# exp30dc.net
KiCad netlist of a schematic drawn in EAGLE
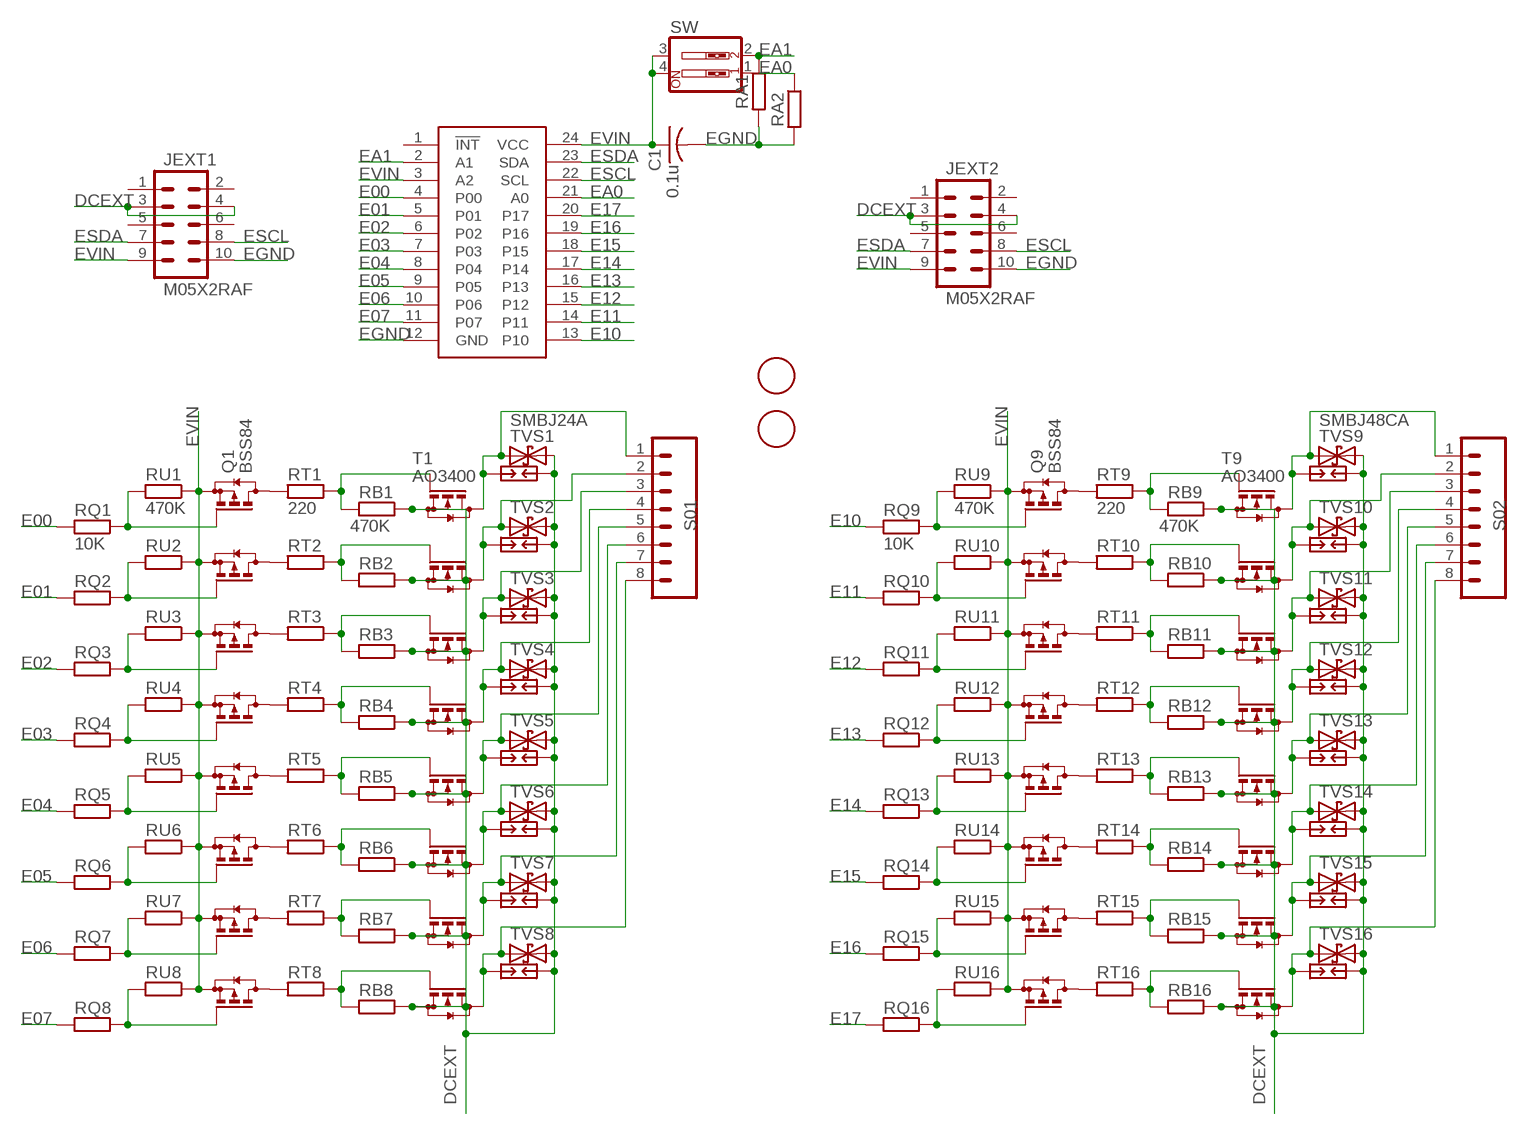
[diagram p0: schematic, sheet 1]

(export (version "E")
  (design (tool "Eeschema 10.0.6"))
  (components
    (comp (ref "C1")
      (value "0.1u")
      (footprint "eagle-import:C0603")
      (libsource (lib "eagle-import") (part "C-USC0603"))
    )
    (comp (ref "JEXT1")
      (value "M05X2RAF")
      (footprint "eagle-import:2X5-RAF")
      (libsource (lib "eagle-import") (part "M05X2RAF"))
    )
    (comp (ref "JEXT2")
      (value "M05X2RAF")
      (footprint "eagle-import:2X5-RAF")
      (libsource (lib "eagle-import") (part "M05X2RAF"))
    )
    (comp (ref "PCF8575")
      (value "PCF8575")
      (footprint "eagle-import:SSOP24")
      (libsource (lib "eagle-import") (part "PCF8575"))
    )
    (comp (ref "Q1")
      (value "BSS84")
      (footprint "eagle-import:SOT23")
      (libsource (lib "eagle-import") (part "BSS84"))
    )
    (comp (ref "Q2")
      (value "BSS84")
      (footprint "eagle-import:SOT23")
      (libsource (lib "eagle-import") (part "BSS84"))
    )
    (comp (ref "Q3")
      (value "BSS84")
      (footprint "eagle-import:SOT23")
      (libsource (lib "eagle-import") (part "BSS84"))
    )
    (comp (ref "Q4")
      (value "BSS84")
      (footprint "eagle-import:SOT23")
      (libsource (lib "eagle-import") (part "BSS84"))
    )
    (comp (ref "Q5")
      (value "BSS84")
      (footprint "eagle-import:SOT23")
      (libsource (lib "eagle-import") (part "BSS84"))
    )
    (comp (ref "Q6")
      (value "BSS84")
      (footprint "eagle-import:SOT23")
      (libsource (lib "eagle-import") (part "BSS84"))
    )
    (comp (ref "Q7")
      (value "BSS84")
      (footprint "eagle-import:SOT23")
      (libsource (lib "eagle-import") (part "BSS84"))
    )
    (comp (ref "Q8")
      (value "BSS84")
      (footprint "eagle-import:SOT23")
      (libsource (lib "eagle-import") (part "BSS84"))
    )
    (comp (ref "Q9")
      (value "BSS84")
      (footprint "eagle-import:SOT23")
      (libsource (lib "eagle-import") (part "BSS84"))
    )
    (comp (ref "Q10")
      (value "BSS84")
      (footprint "eagle-import:SOT23")
      (libsource (lib "eagle-import") (part "BSS84"))
    )
    (comp (ref "Q11")
      (value "BSS84")
      (footprint "eagle-import:SOT23")
      (libsource (lib "eagle-import") (part "BSS84"))
    )
    (comp (ref "Q12")
      (value "BSS84")
      (footprint "eagle-import:SOT23")
      (libsource (lib "eagle-import") (part "BSS84"))
    )
    (comp (ref "Q13")
      (value "BSS84")
      (footprint "eagle-import:SOT23")
      (libsource (lib "eagle-import") (part "BSS84"))
    )
    (comp (ref "Q14")
      (value "BSS84")
      (footprint "eagle-import:SOT23")
      (libsource (lib "eagle-import") (part "BSS84"))
    )
    (comp (ref "Q15")
      (value "BSS84")
      (footprint "eagle-import:SOT23")
      (libsource (lib "eagle-import") (part "BSS84"))
    )
    (comp (ref "Q16")
      (value "BSS84")
      (footprint "eagle-import:SOT23")
      (libsource (lib "eagle-import") (part "BSS84"))
    )
    (comp (ref "RA1")
      (value "10K")
      (footprint "eagle-import:R0603")
      (libsource (lib "eagle-import") (part "R-EU_R0603"))
    )
    (comp (ref "RA2")
      (value "10K")
      (footprint "eagle-import:R0603")
      (libsource (lib "eagle-import") (part "R-EU_R0603"))
    )
    (comp (ref "RB1")
      (value "470K")
      (footprint "eagle-import:R0603")
      (libsource (lib "eagle-import") (part "R-EU_R0603"))
    )
    (comp (ref "RB2")
      (value "470K")
      (footprint "eagle-import:R0603")
      (libsource (lib "eagle-import") (part "R-EU_R0603"))
    )
    (comp (ref "RB3")
      (value "470K")
      (footprint "eagle-import:R0603")
      (libsource (lib "eagle-import") (part "R-EU_R0603"))
    )
    (comp (ref "RB4")
      (value "470K")
      (footprint "eagle-import:R0603")
      (libsource (lib "eagle-import") (part "R-EU_R0603"))
    )
    (comp (ref "RB5")
      (value "470K")
      (footprint "eagle-import:R0603")
      (libsource (lib "eagle-import") (part "R-EU_R0603"))
    )
    (comp (ref "RB6")
      (value "470K")
      (footprint "eagle-import:R0603")
      (libsource (lib "eagle-import") (part "R-EU_R0603"))
    )
    (comp (ref "RB7")
      (value "470K")
      (footprint "eagle-import:R0603")
      (libsource (lib "eagle-import") (part "R-EU_R0603"))
    )
    (comp (ref "RB8")
      (value "470K")
      (footprint "eagle-import:R0603")
      (libsource (lib "eagle-import") (part "R-EU_R0603"))
    )
    (comp (ref "RB9")
      (value "470K")
      (footprint "eagle-import:R0603")
      (libsource (lib "eagle-import") (part "R-EU_R0603"))
    )
    (comp (ref "RB10")
      (value "470K")
      (footprint "eagle-import:R0603")
      (libsource (lib "eagle-import") (part "R-EU_R0603"))
    )
    (comp (ref "RB11")
      (value "470K")
      (footprint "eagle-import:R0603")
      (libsource (lib "eagle-import") (part "R-EU_R0603"))
    )
    (comp (ref "RB12")
      (value "470K")
      (footprint "eagle-import:R0603")
      (libsource (lib "eagle-import") (part "R-EU_R0603"))
    )
    (comp (ref "RB13")
      (value "470K")
      (footprint "eagle-import:R0603")
      (libsource (lib "eagle-import") (part "R-EU_R0603"))
    )
    (comp (ref "RB14")
      (value "470K")
      (footprint "eagle-import:R0603")
      (libsource (lib "eagle-import") (part "R-EU_R0603"))
    )
    (comp (ref "RB15")
      (value "470K")
      (footprint "eagle-import:R0603")
      (libsource (lib "eagle-import") (part "R-EU_R0603"))
    )
    (comp (ref "RB16")
      (value "470K")
      (footprint "eagle-import:R0603")
      (libsource (lib "eagle-import") (part "R-EU_R0603"))
    )
    (comp (ref "RQ1")
      (value "10K")
      (footprint "eagle-import:R0603")
      (libsource (lib "eagle-import") (part "R-EU_R0603"))
    )
    (comp (ref "RQ2")
      (value "10K")
      (footprint "eagle-import:R0603")
      (libsource (lib "eagle-import") (part "R-EU_R0603"))
    )
    (comp (ref "RQ3")
      (value "10K")
      (footprint "eagle-import:R0603")
      (libsource (lib "eagle-import") (part "R-EU_R0603"))
    )
    (comp (ref "RQ4")
      (value "10K")
      (footprint "eagle-import:R0603")
      (libsource (lib "eagle-import") (part "R-EU_R0603"))
    )
    (comp (ref "RQ5")
      (value "10K")
      (footprint "eagle-import:R0603")
      (libsource (lib "eagle-import") (part "R-EU_R0603"))
    )
    (comp (ref "RQ6")
      (value "10K")
      (footprint "eagle-import:R0603")
      (libsource (lib "eagle-import") (part "R-EU_R0603"))
    )
    (comp (ref "RQ7")
      (value "10K")
      (footprint "eagle-import:R0603")
      (libsource (lib "eagle-import") (part "R-EU_R0603"))
    )
    (comp (ref "RQ8")
      (value "10K")
      (footprint "eagle-import:R0603")
      (libsource (lib "eagle-import") (part "R-EU_R0603"))
    )
    (comp (ref "RQ9")
      (value "10K")
      (footprint "eagle-import:R0603")
      (libsource (lib "eagle-import") (part "R-EU_R0603"))
    )
    (comp (ref "RQ10")
      (value "10K")
      (footprint "eagle-import:R0603")
      (libsource (lib "eagle-import") (part "R-EU_R0603"))
    )
    (comp (ref "RQ11")
      (value "10K")
      (footprint "eagle-import:R0603")
      (libsource (lib "eagle-import") (part "R-EU_R0603"))
    )
    (comp (ref "RQ12")
      (value "10K")
      (footprint "eagle-import:R0603")
      (libsource (lib "eagle-import") (part "R-EU_R0603"))
    )
    (comp (ref "RQ13")
      (value "10K")
      (footprint "eagle-import:R0603")
      (libsource (lib "eagle-import") (part "R-EU_R0603"))
    )
    (comp (ref "RQ14")
      (value "10K")
      (footprint "eagle-import:R0603")
      (libsource (lib "eagle-import") (part "R-EU_R0603"))
    )
    (comp (ref "RQ15")
      (value "10K")
      (footprint "eagle-import:R0603")
      (libsource (lib "eagle-import") (part "R-EU_R0603"))
    )
    (comp (ref "RQ16")
      (value "10K")
      (footprint "eagle-import:R0603")
      (libsource (lib "eagle-import") (part "R-EU_R0603"))
    )
    (comp (ref "RT1")
      (value "220")
      (footprint "eagle-import:R0603")
      (libsource (lib "eagle-import") (part "R-EU_R0603"))
    )
    (comp (ref "RT2")
      (value "220")
      (footprint "eagle-import:R0603")
      (libsource (lib "eagle-import") (part "R-EU_R0603"))
    )
    (comp (ref "RT3")
      (value "220")
      (footprint "eagle-import:R0603")
      (libsource (lib "eagle-import") (part "R-EU_R0603"))
    )
    (comp (ref "RT4")
      (value "220")
      (footprint "eagle-import:R0603")
      (libsource (lib "eagle-import") (part "R-EU_R0603"))
    )
    (comp (ref "RT5")
      (value "220")
      (footprint "eagle-import:R0603")
      (libsource (lib "eagle-import") (part "R-EU_R0603"))
    )
    (comp (ref "RT6")
      (value "220")
      (footprint "eagle-import:R0603")
      (libsource (lib "eagle-import") (part "R-EU_R0603"))
    )
    (comp (ref "RT7")
      (value "220")
      (footprint "eagle-import:R0603")
      (libsource (lib "eagle-import") (part "R-EU_R0603"))
    )
    (comp (ref "RT8")
      (value "220")
      (footprint "eagle-import:R0603")
      (libsource (lib "eagle-import") (part "R-EU_R0603"))
    )
    (comp (ref "RT9")
      (value "220")
      (footprint "eagle-import:R0603")
      (libsource (lib "eagle-import") (part "R-EU_R0603"))
    )
    (comp (ref "RT10")
      (value "220")
      (footprint "eagle-import:R0603")
      (libsource (lib "eagle-import") (part "R-EU_R0603"))
    )
    (comp (ref "RT11")
      (value "220")
      (footprint "eagle-import:R0603")
      (libsource (lib "eagle-import") (part "R-EU_R0603"))
    )
    (comp (ref "RT12")
      (value "220")
      (footprint "eagle-import:R0603")
      (libsource (lib "eagle-import") (part "R-EU_R0603"))
    )
    (comp (ref "RT13")
      (value "220")
      (footprint "eagle-import:R0603")
      (libsource (lib "eagle-import") (part "R-EU_R0603"))
    )
    (comp (ref "RT14")
      (value "220")
      (footprint "eagle-import:R0603")
      (libsource (lib "eagle-import") (part "R-EU_R0603"))
    )
    (comp (ref "RT15")
      (value "220")
      (footprint "eagle-import:R0603")
      (libsource (lib "eagle-import") (part "R-EU_R0603"))
    )
    (comp (ref "RT16")
      (value "220")
      (footprint "eagle-import:R0603")
      (libsource (lib "eagle-import") (part "R-EU_R0603"))
    )
    (comp (ref "RU1")
      (value "470K")
      (footprint "eagle-import:R0603")
      (libsource (lib "eagle-import") (part "R-EU_R0603"))
    )
    (comp (ref "RU2")
      (value "470K")
      (footprint "eagle-import:R0603")
      (libsource (lib "eagle-import") (part "R-EU_R0603"))
    )
    (comp (ref "RU3")
      (value "470K")
      (footprint "eagle-import:R0603")
      (libsource (lib "eagle-import") (part "R-EU_R0603"))
    )
    (comp (ref "RU4")
      (value "470K")
      (footprint "eagle-import:R0603")
      (libsource (lib "eagle-import") (part "R-EU_R0603"))
    )
    (comp (ref "RU5")
      (value "470K")
      (footprint "eagle-import:R0603")
      (libsource (lib "eagle-import") (part "R-EU_R0603"))
    )
    (comp (ref "RU6")
      (value "470K")
      (footprint "eagle-import:R0603")
      (libsource (lib "eagle-import") (part "R-EU_R0603"))
    )
    (comp (ref "RU7")
      (value "470K")
      (footprint "eagle-import:R0603")
      (libsource (lib "eagle-import") (part "R-EU_R0603"))
    )
    (comp (ref "RU8")
      (value "470K")
      (footprint "eagle-import:R0603")
      (libsource (lib "eagle-import") (part "R-EU_R0603"))
    )
    (comp (ref "RU9")
      (value "470K")
      (footprint "eagle-import:R0603")
      (libsource (lib "eagle-import") (part "R-EU_R0603"))
    )
    (comp (ref "RU10")
      (value "470K")
      (footprint "eagle-import:R0603")
      (libsource (lib "eagle-import") (part "R-EU_R0603"))
    )
    (comp (ref "RU11")
      (value "470K")
      (footprint "eagle-import:R0603")
      (libsource (lib "eagle-import") (part "R-EU_R0603"))
    )
    (comp (ref "RU12")
      (value "470K")
      (footprint "eagle-import:R0603")
      (libsource (lib "eagle-import") (part "R-EU_R0603"))
    )
    (comp (ref "RU13")
      (value "470K")
      (footprint "eagle-import:R0603")
      (libsource (lib "eagle-import") (part "R-EU_R0603"))
    )
    (comp (ref "RU14")
      (value "470K")
      (footprint "eagle-import:R0603")
      (libsource (lib "eagle-import") (part "R-EU_R0603"))
    )
    (comp (ref "RU15")
      (value "470K")
      (footprint "eagle-import:R0603")
      (libsource (lib "eagle-import") (part "R-EU_R0603"))
    )
    (comp (ref "RU16")
      (value "470K")
      (footprint "eagle-import:R0603")
      (libsource (lib "eagle-import") (part "R-EU_R0603"))
    )
    (comp (ref "S01")
      (value "M085MM-8")
      (footprint "eagle-import:SCREWTERMINAL-5MM-8")
      (libsource (lib "eagle-import") (part "M085MM-8"))
    )
    (comp (ref "S02")
      (value "M085MM-8")
      (footprint "eagle-import:SCREWTERMINAL-5MM-8")
      (libsource (lib "eagle-import") (part "M085MM-8"))
    )
    (comp (ref "SP1")
      (value "PCB-SGAP")
      (footprint "eagle-import:PCB-SGAP")
      (libsource (lib "eagle-import") (part "PCB-SGAP"))
    )
    (comp (ref "SP2")
      (value "PCB-SGAP")
      (footprint "eagle-import:PCB-SGAP")
      (libsource (lib "eagle-import") (part "PCB-SGAP"))
    )
    (comp (ref "SP3")
      (value "PCB-SGAP")
      (footprint "eagle-import:PCB-SGAP")
      (libsource (lib "eagle-import") (part "PCB-SGAP"))
    )
    (comp (ref "SP4")
      (value "PCB-SGAP")
      (footprint "eagle-import:PCB-SGAP")
      (libsource (lib "eagle-import") (part "PCB-SGAP"))
    )
    (comp (ref "SP5")
      (value "PCB-SGAP")
      (footprint "eagle-import:PCB-SGAP")
      (libsource (lib "eagle-import") (part "PCB-SGAP"))
    )
    (comp (ref "SP6")
      (value "PCB-SGAP")
      (footprint "eagle-import:PCB-SGAP")
      (libsource (lib "eagle-import") (part "PCB-SGAP"))
    )
    (comp (ref "SP7")
      (value "PCB-SGAP")
      (footprint "eagle-import:PCB-SGAP")
      (libsource (lib "eagle-import") (part "PCB-SGAP"))
    )
    (comp (ref "SP8")
      (value "PCB-SGAP")
      (footprint "eagle-import:PCB-SGAP")
      (libsource (lib "eagle-import") (part "PCB-SGAP"))
    )
    (comp (ref "SP9")
      (value "PCB-SGAP")
      (footprint "eagle-import:PCB-SGAP")
      (libsource (lib "eagle-import") (part "PCB-SGAP"))
    )
    (comp (ref "SP10")
      (value "PCB-SGAP")
      (footprint "eagle-import:PCB-SGAP")
      (libsource (lib "eagle-import") (part "PCB-SGAP"))
    )
    (comp (ref "SP11")
      (value "PCB-SGAP")
      (footprint "eagle-import:PCB-SGAP")
      (libsource (lib "eagle-import") (part "PCB-SGAP"))
    )
    (comp (ref "SP12")
      (value "PCB-SGAP")
      (footprint "eagle-import:PCB-SGAP")
      (libsource (lib "eagle-import") (part "PCB-SGAP"))
    )
    (comp (ref "SP13")
      (value "PCB-SGAP")
      (footprint "eagle-import:PCB-SGAP")
      (libsource (lib "eagle-import") (part "PCB-SGAP"))
    )
    (comp (ref "SP14")
      (value "PCB-SGAP")
      (footprint "eagle-import:PCB-SGAP")
      (libsource (lib "eagle-import") (part "PCB-SGAP"))
    )
    (comp (ref "SP15")
      (value "PCB-SGAP")
      (footprint "eagle-import:PCB-SGAP")
      (libsource (lib "eagle-import") (part "PCB-SGAP"))
    )
    (comp (ref "SP16")
      (value "PCB-SGAP")
      (footprint "eagle-import:PCB-SGAP")
      (libsource (lib "eagle-import") (part "PCB-SGAP"))
    )
    (comp (ref "SW")
      (value "SW_DIP-2")
      (footprint "eagle-import:DIPSWITCH-02")
      (libsource (lib "eagle-import") (part "SW_DIP-2"))
    )
    (comp (ref "T1")
      (value "AO3400")
      (footprint "eagle-import:SOT23")
      (libsource (lib "eagle-import") (part "BSS123"))
    )
    (comp (ref "T2")
      (value "AO3400")
      (footprint "eagle-import:SOT23")
      (libsource (lib "eagle-import") (part "BSS123"))
    )
    (comp (ref "T3")
      (value "AO3400")
      (footprint "eagle-import:SOT23")
      (libsource (lib "eagle-import") (part "BSS123"))
    )
    (comp (ref "T4")
      (value "AO3400")
      (footprint "eagle-import:SOT23")
      (libsource (lib "eagle-import") (part "BSS123"))
    )
    (comp (ref "T5")
      (value "AO3400")
      (footprint "eagle-import:SOT23")
      (libsource (lib "eagle-import") (part "BSS123"))
    )
    (comp (ref "T6")
      (value "AO3400")
      (footprint "eagle-import:SOT23")
      (libsource (lib "eagle-import") (part "BSS123"))
    )
    (comp (ref "T7")
      (value "AO3400")
      (footprint "eagle-import:SOT23")
      (libsource (lib "eagle-import") (part "BSS123"))
    )
    (comp (ref "T8")
      (value "AO3400")
      (footprint "eagle-import:SOT23")
      (libsource (lib "eagle-import") (part "BSS123"))
    )
    (comp (ref "T9")
      (value "AO3400")
      (footprint "eagle-import:SOT23")
      (libsource (lib "eagle-import") (part "BSS123"))
    )
    (comp (ref "T10")
      (value "AO3400")
      (footprint "eagle-import:SOT23")
      (libsource (lib "eagle-import") (part "BSS123"))
    )
    (comp (ref "T11")
      (value "AO3400")
      (footprint "eagle-import:SOT23")
      (libsource (lib "eagle-import") (part "BSS123"))
    )
    (comp (ref "T12")
      (value "AO3400")
      (footprint "eagle-import:SOT23")
      (libsource (lib "eagle-import") (part "BSS123"))
    )
    (comp (ref "T13")
      (value "AO3400")
      (footprint "eagle-import:SOT23")
      (libsource (lib "eagle-import") (part "BSS123"))
    )
    (comp (ref "T14")
      (value "AO3400")
      (footprint "eagle-import:SOT23")
      (libsource (lib "eagle-import") (part "BSS123"))
    )
    (comp (ref "T15")
      (value "AO3400")
      (footprint "eagle-import:SOT23")
      (libsource (lib "eagle-import") (part "BSS123"))
    )
    (comp (ref "T16")
      (value "AO3400")
      (footprint "eagle-import:SOT23")
      (libsource (lib "eagle-import") (part "BSS123"))
    )
    (comp (ref "TVS1")
      (value "SMBJ24A")
      (footprint "eagle-import:SMB")
      (libsource (lib "eagle-import") (part "TVSSMB"))
    )
    (comp (ref "TVS2")
      (value "TVSSMB")
      (footprint "eagle-import:SMB")
      (libsource (lib "eagle-import") (part "TVSSMB"))
    )
    (comp (ref "TVS3")
      (value "TVSSMB")
      (footprint "eagle-import:SMB")
      (libsource (lib "eagle-import") (part "TVSSMB"))
    )
    (comp (ref "TVS4")
      (value "TVSSMB")
      (footprint "eagle-import:SMB")
      (libsource (lib "eagle-import") (part "TVSSMB"))
    )
    (comp (ref "TVS5")
      (value "TVSSMB")
      (footprint "eagle-import:SMB")
      (libsource (lib "eagle-import") (part "TVSSMB"))
    )
    (comp (ref "TVS6")
      (value "TVSSMB")
      (footprint "eagle-import:SMB")
      (libsource (lib "eagle-import") (part "TVSSMB"))
    )
    (comp (ref "TVS7")
      (value "TVSSMB")
      (footprint "eagle-import:SMB")
      (libsource (lib "eagle-import") (part "TVSSMB"))
    )
    (comp (ref "TVS8")
      (value "TVSSMB")
      (footprint "eagle-import:SMB")
      (libsource (lib "eagle-import") (part "TVSSMB"))
    )
    (comp (ref "TVS9")
      (value "SMBJ48CA")
      (footprint "eagle-import:SMB")
      (libsource (lib "eagle-import") (part "TVSSMB"))
    )
    (comp (ref "TVS10")
      (value "TVSSMB")
      (footprint "eagle-import:SMB")
      (libsource (lib "eagle-import") (part "TVSSMB"))
    )
    (comp (ref "TVS11")
      (value "TVSSMB")
      (footprint "eagle-import:SMB")
      (libsource (lib "eagle-import") (part "TVSSMB"))
    )
    (comp (ref "TVS12")
      (value "TVSSMB")
      (footprint "eagle-import:SMB")
      (libsource (lib "eagle-import") (part "TVSSMB"))
    )
    (comp (ref "TVS13")
      (value "TVSSMB")
      (footprint "eagle-import:SMB")
      (libsource (lib "eagle-import") (part "TVSSMB"))
    )
    (comp (ref "TVS14")
      (value "TVSSMB")
      (footprint "eagle-import:SMB")
      (libsource (lib "eagle-import") (part "TVSSMB"))
    )
    (comp (ref "TVS15")
      (value "TVSSMB")
      (footprint "eagle-import:SMB")
      (libsource (lib "eagle-import") (part "TVSSMB"))
    )
    (comp (ref "TVS16")
      (value "TVSSMB")
      (footprint "eagle-import:SMB")
      (libsource (lib "eagle-import") (part "TVSSMB"))
    )
    (comp (ref "U$1")
      (value "FIDUCIAL")
      (footprint "eagle-import:FIDUCIAL_1MM")
      (libsource (lib "eagle-import") (part "FIDUCIAL"))
    )
    (comp (ref "U$2")
      (value "FIDUCIAL")
      (footprint "eagle-import:FIDUCIAL_1MM")
      (libsource (lib "eagle-import") (part "FIDUCIAL"))
    )
  )
  (nets
    (net (code "1") (name "/DCEXT") (class "Default")
      (node (ref "JEXT1") (pin "3") (pinfunction "3_3") (pintype "passive"))
      (node (ref "JEXT1") (pin "4") (pinfunction "4_4") (pintype "passive"))
      (node (ref "JEXT2") (pin "3") (pinfunction "3_3") (pintype "passive"))
      (node (ref "JEXT2") (pin "4") (pinfunction "4_4") (pintype "passive"))
      (node (ref "RB1") (pin "1") (pinfunction "1_1") (pintype "passive"))
      (node (ref "RB10") (pin "1") (pinfunction "1_1") (pintype "passive"))
      (node (ref "RB11") (pin "1") (pinfunction "1_1") (pintype "passive"))
      (node (ref "RB12") (pin "1") (pinfunction "1_1") (pintype "passive"))
      (node (ref "RB13") (pin "1") (pinfunction "1_1") (pintype "passive"))
      (node (ref "RB14") (pin "1") (pinfunction "1_1") (pintype "passive"))
      (node (ref "RB15") (pin "1") (pinfunction "1_1") (pintype "passive"))
      (node (ref "RB16") (pin "1") (pinfunction "1_1") (pintype "passive"))
      (node (ref "RB2") (pin "1") (pinfunction "1_1") (pintype "passive"))
      (node (ref "RB3") (pin "1") (pinfunction "1_1") (pintype "passive"))
      (node (ref "RB4") (pin "1") (pinfunction "1_1") (pintype "passive"))
      (node (ref "RB5") (pin "1") (pinfunction "1_1") (pintype "passive"))
      (node (ref "RB6") (pin "1") (pinfunction "1_1") (pintype "passive"))
      (node (ref "RB7") (pin "1") (pinfunction "1_1") (pintype "passive"))
      (node (ref "RB8") (pin "1") (pinfunction "1_1") (pintype "passive"))
      (node (ref "RB9") (pin "1") (pinfunction "1_1") (pintype "passive"))
      (node (ref "SP1") (pin "1") (pinfunction "1_1") (pintype "passive"))
      (node (ref "SP10") (pin "1") (pinfunction "1_1") (pintype "passive"))
      (node (ref "SP11") (pin "1") (pinfunction "1_1") (pintype "passive"))
      (node (ref "SP12") (pin "1") (pinfunction "1_1") (pintype "passive"))
      (node (ref "SP13") (pin "1") (pinfunction "1_1") (pintype "passive"))
      (node (ref "SP14") (pin "1") (pinfunction "1_1") (pintype "passive"))
      (node (ref "SP15") (pin "1") (pinfunction "1_1") (pintype "passive"))
      (node (ref "SP16") (pin "1") (pinfunction "1_1") (pintype "passive"))
      (node (ref "SP2") (pin "1") (pinfunction "1_1") (pintype "passive"))
      (node (ref "SP3") (pin "1") (pinfunction "1_1") (pintype "passive"))
      (node (ref "SP4") (pin "1") (pinfunction "1_1") (pintype "passive"))
      (node (ref "SP5") (pin "1") (pinfunction "1_1") (pintype "passive"))
      (node (ref "SP6") (pin "1") (pinfunction "1_1") (pintype "passive"))
      (node (ref "SP7") (pin "1") (pinfunction "1_1") (pintype "passive"))
      (node (ref "SP8") (pin "1") (pinfunction "1_1") (pintype "passive"))
      (node (ref "SP9") (pin "1") (pinfunction "1_1") (pintype "passive"))
      (node (ref "T1") (pin "2") (pinfunction "S_2") (pintype "passive"))
      (node (ref "T10") (pin "2") (pinfunction "S_2") (pintype "passive"))
      (node (ref "T11") (pin "2") (pinfunction "S_2") (pintype "passive"))
      (node (ref "T12") (pin "2") (pinfunction "S_2") (pintype "passive"))
      (node (ref "T13") (pin "2") (pinfunction "S_2") (pintype "passive"))
      (node (ref "T14") (pin "2") (pinfunction "S_2") (pintype "passive"))
      (node (ref "T15") (pin "2") (pinfunction "S_2") (pintype "passive"))
      (node (ref "T16") (pin "2") (pinfunction "S_2") (pintype "passive"))
      (node (ref "T2") (pin "2") (pinfunction "S_2") (pintype "passive"))
      (node (ref "T3") (pin "2") (pinfunction "S_2") (pintype "passive"))
      (node (ref "T4") (pin "2") (pinfunction "S_2") (pintype "passive"))
      (node (ref "T5") (pin "2") (pinfunction "S_2") (pintype "passive"))
      (node (ref "T6") (pin "2") (pinfunction "S_2") (pintype "passive"))
      (node (ref "T7") (pin "2") (pinfunction "S_2") (pintype "passive"))
      (node (ref "T8") (pin "2") (pinfunction "S_2") (pintype "passive"))
      (node (ref "T9") (pin "2") (pinfunction "S_2") (pintype "passive"))
      (node (ref "TVS1") (pin "C") (pinfunction "C_C") (pintype "passive"))
      (node (ref "TVS10") (pin "C") (pinfunction "C_C") (pintype "passive"))
      (node (ref "TVS11") (pin "C") (pinfunction "C_C") (pintype "passive"))
      (node (ref "TVS12") (pin "C") (pinfunction "C_C") (pintype "passive"))
      (node (ref "TVS13") (pin "C") (pinfunction "C_C") (pintype "passive"))
      (node (ref "TVS14") (pin "C") (pinfunction "C_C") (pintype "passive"))
      (node (ref "TVS15") (pin "C") (pinfunction "C_C") (pintype "passive"))
      (node (ref "TVS16") (pin "C") (pinfunction "C_C") (pintype "passive"))
      (node (ref "TVS2") (pin "C") (pinfunction "C_C") (pintype "passive"))
      (node (ref "TVS3") (pin "C") (pinfunction "C_C") (pintype "passive"))
      (node (ref "TVS4") (pin "C") (pinfunction "C_C") (pintype "passive"))
      (node (ref "TVS5") (pin "C") (pinfunction "C_C") (pintype "passive"))
      (node (ref "TVS6") (pin "C") (pinfunction "C_C") (pintype "passive"))
      (node (ref "TVS7") (pin "C") (pinfunction "C_C") (pintype "passive"))
      (node (ref "TVS8") (pin "C") (pinfunction "C_C") (pintype "passive"))
      (node (ref "TVS9") (pin "C") (pinfunction "C_C") (pintype "passive"))
    )
    (net (code "2") (name "/E00") (class "Default")
      (node (ref "PCF8575") (pin "4") (pinfunction "P00_4") (pintype "bidirectional"))
      (node (ref "RQ1") (pin "2") (pinfunction "2_2") (pintype "passive"))
    )
    (net (code "3") (name "/E01") (class "Default")
      (node (ref "PCF8575") (pin "5") (pinfunction "P01_5") (pintype "bidirectional"))
      (node (ref "RQ2") (pin "2") (pinfunction "2_2") (pintype "passive"))
    )
    (net (code "4") (name "/E02") (class "Default")
      (node (ref "PCF8575") (pin "6") (pinfunction "P02_6") (pintype "bidirectional"))
      (node (ref "RQ3") (pin "2") (pinfunction "2_2") (pintype "passive"))
    )
    (net (code "5") (name "/E03") (class "Default")
      (node (ref "PCF8575") (pin "7") (pinfunction "P03_7") (pintype "bidirectional"))
      (node (ref "RQ4") (pin "2") (pinfunction "2_2") (pintype "passive"))
    )
    (net (code "6") (name "/E04") (class "Default")
      (node (ref "PCF8575") (pin "8") (pinfunction "P04_8") (pintype "bidirectional"))
      (node (ref "RQ5") (pin "2") (pinfunction "2_2") (pintype "passive"))
    )
    (net (code "7") (name "/E05") (class "Default")
      (node (ref "PCF8575") (pin "9") (pinfunction "P05_9") (pintype "bidirectional"))
      (node (ref "RQ6") (pin "2") (pinfunction "2_2") (pintype "passive"))
    )
    (net (code "8") (name "/E06") (class "Default")
      (node (ref "PCF8575") (pin "10") (pinfunction "P06_10") (pintype "bidirectional"))
      (node (ref "RQ7") (pin "2") (pinfunction "2_2") (pintype "passive"))
    )
    (net (code "9") (name "/E07") (class "Default")
      (node (ref "PCF8575") (pin "11") (pinfunction "P07_11") (pintype "bidirectional"))
      (node (ref "RQ8") (pin "2") (pinfunction "2_2") (pintype "passive"))
    )
    (net (code "10") (name "/E10") (class "Default")
      (node (ref "PCF8575") (pin "13") (pinfunction "P10_13") (pintype "bidirectional"))
      (node (ref "RQ9") (pin "2") (pinfunction "2_2") (pintype "passive"))
    )
    (net (code "11") (name "/E11") (class "Default")
      (node (ref "PCF8575") (pin "14") (pinfunction "P11_14") (pintype "bidirectional"))
      (node (ref "RQ10") (pin "2") (pinfunction "2_2") (pintype "passive"))
    )
    (net (code "12") (name "/E12") (class "Default")
      (node (ref "PCF8575") (pin "15") (pinfunction "P12_15") (pintype "bidirectional"))
      (node (ref "RQ11") (pin "2") (pinfunction "2_2") (pintype "passive"))
    )
    (net (code "13") (name "/E13") (class "Default")
      (node (ref "PCF8575") (pin "16") (pinfunction "P13_16") (pintype "bidirectional"))
      (node (ref "RQ12") (pin "2") (pinfunction "2_2") (pintype "passive"))
    )
    (net (code "14") (name "/E14") (class "Default")
      (node (ref "PCF8575") (pin "17") (pinfunction "P14_17") (pintype "bidirectional"))
      (node (ref "RQ13") (pin "2") (pinfunction "2_2") (pintype "passive"))
    )
    (net (code "15") (name "/E15") (class "Default")
      (node (ref "PCF8575") (pin "18") (pinfunction "P15_18") (pintype "bidirectional"))
      (node (ref "RQ14") (pin "2") (pinfunction "2_2") (pintype "passive"))
    )
    (net (code "16") (name "/E16") (class "Default")
      (node (ref "PCF8575") (pin "19") (pinfunction "P16_19") (pintype "bidirectional"))
      (node (ref "RQ15") (pin "2") (pinfunction "2_2") (pintype "passive"))
    )
    (net (code "17") (name "/E17") (class "Default")
      (node (ref "PCF8575") (pin "20") (pinfunction "P17_20") (pintype "bidirectional"))
      (node (ref "RQ16") (pin "2") (pinfunction "2_2") (pintype "passive"))
    )
    (net (code "18") (name "/EA0") (class "Default")
      (node (ref "PCF8575") (pin "21") (pinfunction "A0_21") (pintype "bidirectional"))
      (node (ref "RA2") (pin "1") (pinfunction "1_1") (pintype "passive"))
      (node (ref "SW") (pin "1") (pinfunction "1_1") (pintype "passive"))
    )
    (net (code "19") (name "/EA1") (class "Default")
      (node (ref "PCF8575") (pin "2") (pinfunction "A1_2") (pintype "bidirectional"))
      (node (ref "RA1") (pin "1") (pinfunction "1_1") (pintype "passive"))
      (node (ref "SW") (pin "2") (pinfunction "2_2") (pintype "passive"))
    )
    (net (code "20") (name "/EGND") (class "Default")
      (node (ref "C1") (pin "2") (pinfunction "2_2") (pintype "passive"))
      (node (ref "JEXT1") (pin "10") (pinfunction "10_10") (pintype "passive"))
      (node (ref "JEXT2") (pin "10") (pinfunction "10_10") (pintype "passive"))
      (node (ref "PCF8575") (pin "12") (pinfunction "GND_12") (pintype "power_in"))
      (node (ref "RA1") (pin "2") (pinfunction "2_2") (pintype "passive"))
      (node (ref "RA2") (pin "2") (pinfunction "2_2") (pintype "passive"))
    )
    (net (code "21") (name "/ESCL") (class "Default")
      (node (ref "JEXT1") (pin "8") (pinfunction "8_8") (pintype "passive"))
      (node (ref "JEXT2") (pin "8") (pinfunction "8_8") (pintype "passive"))
      (node (ref "PCF8575") (pin "22") (pinfunction "SCL_22") (pintype "bidirectional"))
    )
    (net (code "22") (name "/ESDA") (class "Default")
      (node (ref "JEXT1") (pin "7") (pinfunction "7_7") (pintype "passive"))
      (node (ref "JEXT2") (pin "7") (pinfunction "7_7") (pintype "passive"))
      (node (ref "PCF8575") (pin "23") (pinfunction "SDA_23") (pintype "bidirectional"))
    )
    (net (code "23") (name "/EVIN") (class "Default")
      (node (ref "C1") (pin "1") (pinfunction "1_1") (pintype "passive"))
      (node (ref "JEXT1") (pin "9") (pinfunction "9_9") (pintype "passive"))
      (node (ref "JEXT2") (pin "9") (pinfunction "9_9") (pintype "passive"))
      (node (ref "PCF8575") (pin "24") (pinfunction "VCC_24") (pintype "power_in"))
      (node (ref "PCF8575") (pin "3") (pinfunction "A2_3") (pintype "bidirectional"))
      (node (ref "Q1") (pin "2") (pinfunction "S_2") (pintype "passive"))
      (node (ref "Q10") (pin "2") (pinfunction "S_2") (pintype "passive"))
      (node (ref "Q11") (pin "2") (pinfunction "S_2") (pintype "passive"))
      (node (ref "Q12") (pin "2") (pinfunction "S_2") (pintype "passive"))
      (node (ref "Q13") (pin "2") (pinfunction "S_2") (pintype "passive"))
      (node (ref "Q14") (pin "2") (pinfunction "S_2") (pintype "passive"))
      (node (ref "Q15") (pin "2") (pinfunction "S_2") (pintype "passive"))
      (node (ref "Q16") (pin "2") (pinfunction "S_2") (pintype "passive"))
      (node (ref "Q2") (pin "2") (pinfunction "S_2") (pintype "passive"))
      (node (ref "Q3") (pin "2") (pinfunction "S_2") (pintype "passive"))
      (node (ref "Q4") (pin "2") (pinfunction "S_2") (pintype "passive"))
      (node (ref "Q5") (pin "2") (pinfunction "S_2") (pintype "passive"))
      (node (ref "Q6") (pin "2") (pinfunction "S_2") (pintype "passive"))
      (node (ref "Q7") (pin "2") (pinfunction "S_2") (pintype "passive"))
      (node (ref "Q8") (pin "2") (pinfunction "S_2") (pintype "passive"))
      (node (ref "Q9") (pin "2") (pinfunction "S_2") (pintype "passive"))
      (node (ref "RU1") (pin "1") (pinfunction "1_1") (pintype "passive"))
      (node (ref "RU10") (pin "1") (pinfunction "1_1") (pintype "passive"))
      (node (ref "RU11") (pin "1") (pinfunction "1_1") (pintype "passive"))
      (node (ref "RU12") (pin "1") (pinfunction "1_1") (pintype "passive"))
      (node (ref "RU13") (pin "1") (pinfunction "1_1") (pintype "passive"))
      (node (ref "RU14") (pin "1") (pinfunction "1_1") (pintype "passive"))
      (node (ref "RU15") (pin "1") (pinfunction "1_1") (pintype "passive"))
      (node (ref "RU16") (pin "1") (pinfunction "1_1") (pintype "passive"))
      (node (ref "RU2") (pin "1") (pinfunction "1_1") (pintype "passive"))
      (node (ref "RU3") (pin "1") (pinfunction "1_1") (pintype "passive"))
      (node (ref "RU4") (pin "1") (pinfunction "1_1") (pintype "passive"))
      (node (ref "RU5") (pin "1") (pinfunction "1_1") (pintype "passive"))
      (node (ref "RU6") (pin "1") (pinfunction "1_1") (pintype "passive"))
      (node (ref "RU7") (pin "1") (pinfunction "1_1") (pintype "passive"))
      (node (ref "RU8") (pin "1") (pinfunction "1_1") (pintype "passive"))
      (node (ref "RU9") (pin "1") (pinfunction "1_1") (pintype "passive"))
      (node (ref "SW") (pin "3") (pinfunction "3_3") (pintype "passive"))
      (node (ref "SW") (pin "4") (pinfunction "4_4") (pintype "passive"))
    )
    (net (code "24") (name "Net-(Q1-D)") (class "Default")
      (node (ref "Q1") (pin "3") (pinfunction "D_3") (pintype "passive"))
      (node (ref "RT1") (pin "2") (pinfunction "2_2") (pintype "passive"))
    )
    (net (code "25") (name "Net-(Q1-G)") (class "Default")
      (node (ref "Q1") (pin "1") (pinfunction "G_1") (pintype "passive"))
      (node (ref "RQ1") (pin "1") (pinfunction "1_1") (pintype "passive"))
      (node (ref "RU1") (pin "2") (pinfunction "2_2") (pintype "passive"))
    )
    (net (code "26") (name "Net-(Q2-D)") (class "Default")
      (node (ref "Q2") (pin "3") (pinfunction "D_3") (pintype "passive"))
      (node (ref "RT2") (pin "2") (pinfunction "2_2") (pintype "passive"))
    )
    (net (code "27") (name "Net-(Q2-G)") (class "Default")
      (node (ref "Q2") (pin "1") (pinfunction "G_1") (pintype "passive"))
      (node (ref "RQ2") (pin "1") (pinfunction "1_1") (pintype "passive"))
      (node (ref "RU2") (pin "2") (pinfunction "2_2") (pintype "passive"))
    )
    (net (code "28") (name "Net-(Q3-D)") (class "Default")
      (node (ref "Q3") (pin "3") (pinfunction "D_3") (pintype "passive"))
      (node (ref "RT3") (pin "2") (pinfunction "2_2") (pintype "passive"))
    )
    (net (code "29") (name "Net-(Q3-G)") (class "Default")
      (node (ref "Q3") (pin "1") (pinfunction "G_1") (pintype "passive"))
      (node (ref "RQ3") (pin "1") (pinfunction "1_1") (pintype "passive"))
      (node (ref "RU3") (pin "2") (pinfunction "2_2") (pintype "passive"))
    )
    (net (code "30") (name "Net-(Q4-D)") (class "Default")
      (node (ref "Q4") (pin "3") (pinfunction "D_3") (pintype "passive"))
      (node (ref "RT4") (pin "2") (pinfunction "2_2") (pintype "passive"))
    )
    (net (code "31") (name "Net-(Q4-G)") (class "Default")
      (node (ref "Q4") (pin "1") (pinfunction "G_1") (pintype "passive"))
      (node (ref "RQ4") (pin "1") (pinfunction "1_1") (pintype "passive"))
      (node (ref "RU4") (pin "2") (pinfunction "2_2") (pintype "passive"))
    )
    (net (code "32") (name "Net-(Q5-D)") (class "Default")
      (node (ref "Q5") (pin "3") (pinfunction "D_3") (pintype "passive"))
      (node (ref "RT5") (pin "2") (pinfunction "2_2") (pintype "passive"))
    )
    (net (code "33") (name "Net-(Q5-G)") (class "Default")
      (node (ref "Q5") (pin "1") (pinfunction "G_1") (pintype "passive"))
      (node (ref "RQ5") (pin "1") (pinfunction "1_1") (pintype "passive"))
      (node (ref "RU5") (pin "2") (pinfunction "2_2") (pintype "passive"))
    )
    (net (code "34") (name "Net-(Q6-D)") (class "Default")
      (node (ref "Q6") (pin "3") (pinfunction "D_3") (pintype "passive"))
      (node (ref "RT6") (pin "2") (pinfunction "2_2") (pintype "passive"))
    )
    (net (code "35") (name "Net-(Q6-G)") (class "Default")
      (node (ref "Q6") (pin "1") (pinfunction "G_1") (pintype "passive"))
      (node (ref "RQ6") (pin "1") (pinfunction "1_1") (pintype "passive"))
      (node (ref "RU6") (pin "2") (pinfunction "2_2") (pintype "passive"))
    )
    (net (code "36") (name "Net-(Q7-D)") (class "Default")
      (node (ref "Q7") (pin "3") (pinfunction "D_3") (pintype "passive"))
      (node (ref "RT7") (pin "2") (pinfunction "2_2") (pintype "passive"))
    )
    (net (code "37") (name "Net-(Q7-G)") (class "Default")
      (node (ref "Q7") (pin "1") (pinfunction "G_1") (pintype "passive"))
      (node (ref "RQ7") (pin "1") (pinfunction "1_1") (pintype "passive"))
      (node (ref "RU7") (pin "2") (pinfunction "2_2") (pintype "passive"))
    )
    (net (code "38") (name "Net-(Q8-D)") (class "Default")
      (node (ref "Q8") (pin "3") (pinfunction "D_3") (pintype "passive"))
      (node (ref "RT8") (pin "2") (pinfunction "2_2") (pintype "passive"))
    )
    (net (code "39") (name "Net-(Q8-G)") (class "Default")
      (node (ref "Q8") (pin "1") (pinfunction "G_1") (pintype "passive"))
      (node (ref "RQ8") (pin "1") (pinfunction "1_1") (pintype "passive"))
      (node (ref "RU8") (pin "2") (pinfunction "2_2") (pintype "passive"))
    )
    (net (code "40") (name "Net-(Q9-D)") (class "Default")
      (node (ref "Q9") (pin "3") (pinfunction "D_3") (pintype "passive"))
      (node (ref "RT9") (pin "2") (pinfunction "2_2") (pintype "passive"))
    )
    (net (code "41") (name "Net-(Q9-G)") (class "Default")
      (node (ref "Q9") (pin "1") (pinfunction "G_1") (pintype "passive"))
      (node (ref "RQ9") (pin "1") (pinfunction "1_1") (pintype "passive"))
      (node (ref "RU9") (pin "2") (pinfunction "2_2") (pintype "passive"))
    )
    (net (code "42") (name "Net-(Q10-D)") (class "Default")
      (node (ref "Q10") (pin "3") (pinfunction "D_3") (pintype "passive"))
      (node (ref "RT10") (pin "2") (pinfunction "2_2") (pintype "passive"))
    )
    (net (code "43") (name "Net-(Q10-G)") (class "Default")
      (node (ref "Q10") (pin "1") (pinfunction "G_1") (pintype "passive"))
      (node (ref "RQ10") (pin "1") (pinfunction "1_1") (pintype "passive"))
      (node (ref "RU10") (pin "2") (pinfunction "2_2") (pintype "passive"))
    )
    (net (code "44") (name "Net-(Q11-D)") (class "Default")
      (node (ref "Q11") (pin "3") (pinfunction "D_3") (pintype "passive"))
      (node (ref "RT11") (pin "2") (pinfunction "2_2") (pintype "passive"))
    )
    (net (code "45") (name "Net-(Q11-G)") (class "Default")
      (node (ref "Q11") (pin "1") (pinfunction "G_1") (pintype "passive"))
      (node (ref "RQ11") (pin "1") (pinfunction "1_1") (pintype "passive"))
      (node (ref "RU11") (pin "2") (pinfunction "2_2") (pintype "passive"))
    )
    (net (code "46") (name "Net-(Q12-D)") (class "Default")
      (node (ref "Q12") (pin "3") (pinfunction "D_3") (pintype "passive"))
      (node (ref "RT12") (pin "2") (pinfunction "2_2") (pintype "passive"))
    )
    (net (code "47") (name "Net-(Q12-G)") (class "Default")
      (node (ref "Q12") (pin "1") (pinfunction "G_1") (pintype "passive"))
      (node (ref "RQ12") (pin "1") (pinfunction "1_1") (pintype "passive"))
      (node (ref "RU12") (pin "2") (pinfunction "2_2") (pintype "passive"))
    )
    (net (code "48") (name "Net-(Q13-D)") (class "Default")
      (node (ref "Q13") (pin "3") (pinfunction "D_3") (pintype "passive"))
      (node (ref "RT13") (pin "2") (pinfunction "2_2") (pintype "passive"))
    )
    (net (code "49") (name "Net-(Q13-G)") (class "Default")
      (node (ref "Q13") (pin "1") (pinfunction "G_1") (pintype "passive"))
      (node (ref "RQ13") (pin "1") (pinfunction "1_1") (pintype "passive"))
      (node (ref "RU13") (pin "2") (pinfunction "2_2") (pintype "passive"))
    )
    (net (code "50") (name "Net-(Q14-D)") (class "Default")
      (node (ref "Q14") (pin "3") (pinfunction "D_3") (pintype "passive"))
      (node (ref "RT14") (pin "2") (pinfunction "2_2") (pintype "passive"))
    )
    (net (code "51") (name "Net-(Q14-G)") (class "Default")
      (node (ref "Q14") (pin "1") (pinfunction "G_1") (pintype "passive"))
      (node (ref "RQ14") (pin "1") (pinfunction "1_1") (pintype "passive"))
      (node (ref "RU14") (pin "2") (pinfunction "2_2") (pintype "passive"))
    )
    (net (code "52") (name "Net-(Q15-D)") (class "Default")
      (node (ref "Q15") (pin "3") (pinfunction "D_3") (pintype "passive"))
      (node (ref "RT15") (pin "2") (pinfunction "2_2") (pintype "passive"))
    )
    (net (code "53") (name "Net-(Q15-G)") (class "Default")
      (node (ref "Q15") (pin "1") (pinfunction "G_1") (pintype "passive"))
      (node (ref "RQ15") (pin "1") (pinfunction "1_1") (pintype "passive"))
      (node (ref "RU15") (pin "2") (pinfunction "2_2") (pintype "passive"))
    )
    (net (code "54") (name "Net-(Q16-D)") (class "Default")
      (node (ref "Q16") (pin "3") (pinfunction "D_3") (pintype "passive"))
      (node (ref "RT16") (pin "2") (pinfunction "2_2") (pintype "passive"))
    )
    (net (code "55") (name "Net-(Q16-G)") (class "Default")
      (node (ref "Q16") (pin "1") (pinfunction "G_1") (pintype "passive"))
      (node (ref "RQ16") (pin "1") (pinfunction "1_1") (pintype "passive"))
      (node (ref "RU16") (pin "2") (pinfunction "2_2") (pintype "passive"))
    )
    (net (code "56") (name "Net-(T1-D)") (class "Default")
      (node (ref "S01") (pin "1") (pinfunction "1_1") (pintype "passive"))
      (node (ref "SP1") (pin "2") (pinfunction "2_2") (pintype "passive"))
      (node (ref "T1") (pin "3") (pinfunction "D_3") (pintype "passive"))
      (node (ref "TVS1") (pin "A") (pinfunction "A_A") (pintype "passive"))
    )
    (net (code "57") (name "Net-(T1-G)") (class "Default")
      (node (ref "RB1") (pin "2") (pinfunction "2_2") (pintype "passive"))
      (node (ref "RT1") (pin "1") (pinfunction "1_1") (pintype "passive"))
      (node (ref "T1") (pin "1") (pinfunction "G_1") (pintype "passive"))
    )
    (net (code "58") (name "Net-(T2-D)") (class "Default")
      (node (ref "S01") (pin "2") (pinfunction "2_2") (pintype "passive"))
      (node (ref "SP2") (pin "2") (pinfunction "2_2") (pintype "passive"))
      (node (ref "T2") (pin "3") (pinfunction "D_3") (pintype "passive"))
      (node (ref "TVS2") (pin "A") (pinfunction "A_A") (pintype "passive"))
    )
    (net (code "59") (name "Net-(T2-G)") (class "Default")
      (node (ref "RB2") (pin "2") (pinfunction "2_2") (pintype "passive"))
      (node (ref "RT2") (pin "1") (pinfunction "1_1") (pintype "passive"))
      (node (ref "T2") (pin "1") (pinfunction "G_1") (pintype "passive"))
    )
    (net (code "60") (name "Net-(T3-D)") (class "Default")
      (node (ref "S01") (pin "3") (pinfunction "3_3") (pintype "passive"))
      (node (ref "SP3") (pin "2") (pinfunction "2_2") (pintype "passive"))
      (node (ref "T3") (pin "3") (pinfunction "D_3") (pintype "passive"))
      (node (ref "TVS3") (pin "A") (pinfunction "A_A") (pintype "passive"))
    )
    (net (code "61") (name "Net-(T3-G)") (class "Default")
      (node (ref "RB3") (pin "2") (pinfunction "2_2") (pintype "passive"))
      (node (ref "RT3") (pin "1") (pinfunction "1_1") (pintype "passive"))
      (node (ref "T3") (pin "1") (pinfunction "G_1") (pintype "passive"))
    )
    (net (code "62") (name "Net-(T4-D)") (class "Default")
      (node (ref "S01") (pin "4") (pinfunction "4_4") (pintype "passive"))
      (node (ref "SP4") (pin "2") (pinfunction "2_2") (pintype "passive"))
      (node (ref "T4") (pin "3") (pinfunction "D_3") (pintype "passive"))
      (node (ref "TVS4") (pin "A") (pinfunction "A_A") (pintype "passive"))
    )
    (net (code "63") (name "Net-(T4-G)") (class "Default")
      (node (ref "RB4") (pin "2") (pinfunction "2_2") (pintype "passive"))
      (node (ref "RT4") (pin "1") (pinfunction "1_1") (pintype "passive"))
      (node (ref "T4") (pin "1") (pinfunction "G_1") (pintype "passive"))
    )
    (net (code "64") (name "Net-(T5-D)") (class "Default")
      (node (ref "S01") (pin "5") (pinfunction "5_5") (pintype "passive"))
      (node (ref "SP5") (pin "2") (pinfunction "2_2") (pintype "passive"))
      (node (ref "T5") (pin "3") (pinfunction "D_3") (pintype "passive"))
      (node (ref "TVS5") (pin "A") (pinfunction "A_A") (pintype "passive"))
    )
    (net (code "65") (name "Net-(T5-G)") (class "Default")
      (node (ref "RB5") (pin "2") (pinfunction "2_2") (pintype "passive"))
      (node (ref "RT5") (pin "1") (pinfunction "1_1") (pintype "passive"))
      (node (ref "T5") (pin "1") (pinfunction "G_1") (pintype "passive"))
    )
    (net (code "66") (name "Net-(T6-D)") (class "Default")
      (node (ref "S01") (pin "6") (pinfunction "6_6") (pintype "passive"))
      (node (ref "SP6") (pin "2") (pinfunction "2_2") (pintype "passive"))
      (node (ref "T6") (pin "3") (pinfunction "D_3") (pintype "passive"))
      (node (ref "TVS6") (pin "A") (pinfunction "A_A") (pintype "passive"))
    )
    (net (code "67") (name "Net-(T6-G)") (class "Default")
      (node (ref "RB6") (pin "2") (pinfunction "2_2") (pintype "passive"))
      (node (ref "RT6") (pin "1") (pinfunction "1_1") (pintype "passive"))
      (node (ref "T6") (pin "1") (pinfunction "G_1") (pintype "passive"))
    )
    (net (code "68") (name "Net-(T7-D)") (class "Default")
      (node (ref "S01") (pin "7") (pinfunction "7_7") (pintype "passive"))
      (node (ref "SP7") (pin "2") (pinfunction "2_2") (pintype "passive"))
      (node (ref "T7") (pin "3") (pinfunction "D_3") (pintype "passive"))
      (node (ref "TVS7") (pin "A") (pinfunction "A_A") (pintype "passive"))
    )
    (net (code "69") (name "Net-(T7-G)") (class "Default")
      (node (ref "RB7") (pin "2") (pinfunction "2_2") (pintype "passive"))
      (node (ref "RT7") (pin "1") (pinfunction "1_1") (pintype "passive"))
      (node (ref "T7") (pin "1") (pinfunction "G_1") (pintype "passive"))
    )
    (net (code "70") (name "Net-(T8-D)") (class "Default")
      (node (ref "S01") (pin "8") (pinfunction "8_8") (pintype "passive"))
      (node (ref "SP8") (pin "2") (pinfunction "2_2") (pintype "passive"))
      (node (ref "T8") (pin "3") (pinfunction "D_3") (pintype "passive"))
      (node (ref "TVS8") (pin "A") (pinfunction "A_A") (pintype "passive"))
    )
    (net (code "71") (name "Net-(T8-G)") (class "Default")
      (node (ref "RB8") (pin "2") (pinfunction "2_2") (pintype "passive"))
      (node (ref "RT8") (pin "1") (pinfunction "1_1") (pintype "passive"))
      (node (ref "T8") (pin "1") (pinfunction "G_1") (pintype "passive"))
    )
    (net (code "72") (name "Net-(T9-D)") (class "Default")
      (node (ref "S02") (pin "1") (pinfunction "1_1") (pintype "passive"))
      (node (ref "SP9") (pin "2") (pinfunction "2_2") (pintype "passive"))
      (node (ref "T9") (pin "3") (pinfunction "D_3") (pintype "passive"))
      (node (ref "TVS9") (pin "A") (pinfunction "A_A") (pintype "passive"))
    )
    (net (code "73") (name "Net-(T9-G)") (class "Default")
      (node (ref "RB9") (pin "2") (pinfunction "2_2") (pintype "passive"))
      (node (ref "RT9") (pin "1") (pinfunction "1_1") (pintype "passive"))
      (node (ref "T9") (pin "1") (pinfunction "G_1") (pintype "passive"))
    )
    (net (code "74") (name "Net-(T10-D)") (class "Default")
      (node (ref "S02") (pin "2") (pinfunction "2_2") (pintype "passive"))
      (node (ref "SP10") (pin "2") (pinfunction "2_2") (pintype "passive"))
      (node (ref "T10") (pin "3") (pinfunction "D_3") (pintype "passive"))
      (node (ref "TVS10") (pin "A") (pinfunction "A_A") (pintype "passive"))
    )
    (net (code "75") (name "Net-(T10-G)") (class "Default")
      (node (ref "RB10") (pin "2") (pinfunction "2_2") (pintype "passive"))
      (node (ref "RT10") (pin "1") (pinfunction "1_1") (pintype "passive"))
      (node (ref "T10") (pin "1") (pinfunction "G_1") (pintype "passive"))
    )
    (net (code "76") (name "Net-(T11-D)") (class "Default")
      (node (ref "S02") (pin "3") (pinfunction "3_3") (pintype "passive"))
      (node (ref "SP11") (pin "2") (pinfunction "2_2") (pintype "passive"))
      (node (ref "T11") (pin "3") (pinfunction "D_3") (pintype "passive"))
      (node (ref "TVS11") (pin "A") (pinfunction "A_A") (pintype "passive"))
    )
    (net (code "77") (name "Net-(T11-G)") (class "Default")
      (node (ref "RB11") (pin "2") (pinfunction "2_2") (pintype "passive"))
      (node (ref "RT11") (pin "1") (pinfunction "1_1") (pintype "passive"))
      (node (ref "T11") (pin "1") (pinfunction "G_1") (pintype "passive"))
    )
    (net (code "78") (name "Net-(T12-D)") (class "Default")
      (node (ref "S02") (pin "4") (pinfunction "4_4") (pintype "passive"))
      (node (ref "SP12") (pin "2") (pinfunction "2_2") (pintype "passive"))
      (node (ref "T12") (pin "3") (pinfunction "D_3") (pintype "passive"))
      (node (ref "TVS12") (pin "A") (pinfunction "A_A") (pintype "passive"))
    )
    (net (code "79") (name "Net-(T12-G)") (class "Default")
      (node (ref "RB12") (pin "2") (pinfunction "2_2") (pintype "passive"))
      (node (ref "RT12") (pin "1") (pinfunction "1_1") (pintype "passive"))
      (node (ref "T12") (pin "1") (pinfunction "G_1") (pintype "passive"))
    )
    (net (code "80") (name "Net-(T13-D)") (class "Default")
      (node (ref "S02") (pin "5") (pinfunction "5_5") (pintype "passive"))
      (node (ref "SP13") (pin "2") (pinfunction "2_2") (pintype "passive"))
      (node (ref "T13") (pin "3") (pinfunction "D_3") (pintype "passive"))
      (node (ref "TVS13") (pin "A") (pinfunction "A_A") (pintype "passive"))
    )
    (net (code "81") (name "Net-(T13-G)") (class "Default")
      (node (ref "RB13") (pin "2") (pinfunction "2_2") (pintype "passive"))
      (node (ref "RT13") (pin "1") (pinfunction "1_1") (pintype "passive"))
      (node (ref "T13") (pin "1") (pinfunction "G_1") (pintype "passive"))
    )
    (net (code "82") (name "Net-(T14-D)") (class "Default")
      (node (ref "S02") (pin "6") (pinfunction "6_6") (pintype "passive"))
      (node (ref "SP14") (pin "2") (pinfunction "2_2") (pintype "passive"))
      (node (ref "T14") (pin "3") (pinfunction "D_3") (pintype "passive"))
      (node (ref "TVS14") (pin "A") (pinfunction "A_A") (pintype "passive"))
    )
    (net (code "83") (name "Net-(T14-G)") (class "Default")
      (node (ref "RB14") (pin "2") (pinfunction "2_2") (pintype "passive"))
      (node (ref "RT14") (pin "1") (pinfunction "1_1") (pintype "passive"))
      (node (ref "T14") (pin "1") (pinfunction "G_1") (pintype "passive"))
    )
    (net (code "84") (name "Net-(T15-D)") (class "Default")
      (node (ref "S02") (pin "7") (pinfunction "7_7") (pintype "passive"))
      (node (ref "SP15") (pin "2") (pinfunction "2_2") (pintype "passive"))
      (node (ref "T15") (pin "3") (pinfunction "D_3") (pintype "passive"))
      (node (ref "TVS15") (pin "A") (pinfunction "A_A") (pintype "passive"))
    )
    (net (code "85") (name "Net-(T15-G)") (class "Default")
      (node (ref "RB15") (pin "2") (pinfunction "2_2") (pintype "passive"))
      (node (ref "RT15") (pin "1") (pinfunction "1_1") (pintype "passive"))
      (node (ref "T15") (pin "1") (pinfunction "G_1") (pintype "passive"))
    )
    (net (code "86") (name "Net-(T16-D)") (class "Default")
      (node (ref "S02") (pin "8") (pinfunction "8_8") (pintype "passive"))
      (node (ref "SP16") (pin "2") (pinfunction "2_2") (pintype "passive"))
      (node (ref "T16") (pin "3") (pinfunction "D_3") (pintype "passive"))
      (node (ref "TVS16") (pin "A") (pinfunction "A_A") (pintype "passive"))
    )
    (net (code "87") (name "Net-(T16-G)") (class "Default")
      (node (ref "RB16") (pin "2") (pinfunction "2_2") (pintype "passive"))
      (node (ref "RT16") (pin "1") (pinfunction "1_1") (pintype "passive"))
      (node (ref "T16") (pin "1") (pinfunction "G_1") (pintype "passive"))
    )
    (net (code "88") (name "unconnected-(JEXT1-Pad1)") (class "Default")
      (node (ref "JEXT1") (pin "1") (pinfunction "1_1") (pintype "passive"))
    )
    (net (code "89") (name "unconnected-(JEXT1-Pad2)") (class "Default")
      (node (ref "JEXT1") (pin "2") (pinfunction "2_2") (pintype "passive"))
    )
    (net (code "90") (name "unconnected-(JEXT1-Pad5)") (class "Default")
      (node (ref "JEXT1") (pin "5") (pinfunction "5_5") (pintype "passive"))
    )
    (net (code "91") (name "unconnected-(JEXT1-Pad6)") (class "Default")
      (node (ref "JEXT1") (pin "6") (pinfunction "6_6") (pintype "passive"))
    )
    (net (code "92") (name "unconnected-(JEXT2-Pad1)") (class "Default")
      (node (ref "JEXT2") (pin "1") (pinfunction "1_1") (pintype "passive"))
    )
    (net (code "93") (name "unconnected-(JEXT2-Pad2)") (class "Default")
      (node (ref "JEXT2") (pin "2") (pinfunction "2_2") (pintype "passive"))
    )
    (net (code "94") (name "unconnected-(JEXT2-Pad5)") (class "Default")
      (node (ref "JEXT2") (pin "5") (pinfunction "5_5") (pintype "passive"))
    )
    (net (code "95") (name "unconnected-(JEXT2-Pad6)") (class "Default")
      (node (ref "JEXT2") (pin "6") (pinfunction "6_6") (pintype "passive"))
    )
    (net (code "96") (name "unconnected-(PCF8575-~{INT}-Pad1)") (class "Default")
      (node (ref "PCF8575") (pin "1") (pinfunction "~{INT}_1") (pintype "bidirectional"))
    )
  )
)
